# Hx711_schematic_V1_r1_0.net
KiCad netlist of a schematic drawn in EAGLE
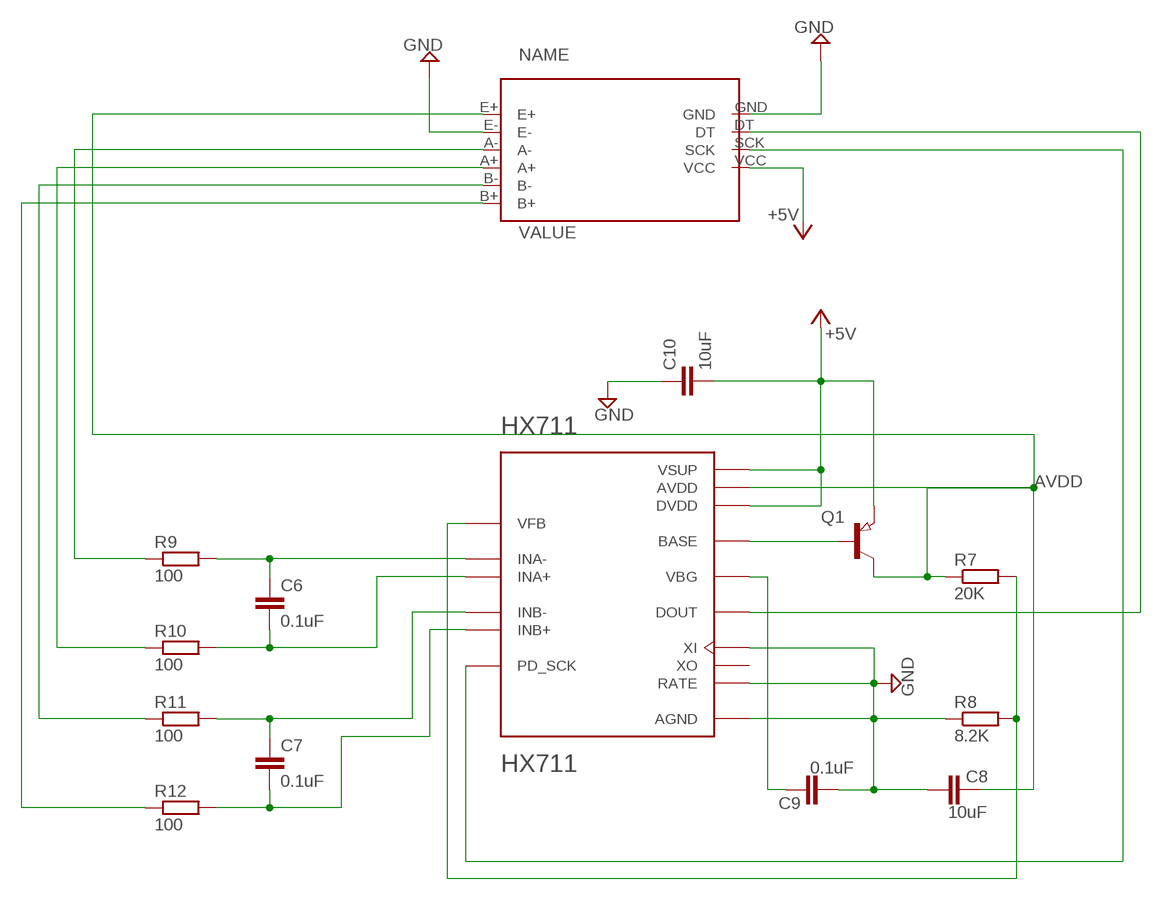
[diagram p0: schematic, sheet 1]

(export (version "E")
  (design (tool "Eeschema 10.0.6"))
  (components
    (comp (ref "C6")
      (value "0.1uF")
      (footprint "eagle-import:C2.5-2")
      (libsource (lib "eagle-import") (part "C2.5/2"))
    )
    (comp (ref "C7")
      (value "0.1uF")
      (footprint "eagle-import:C2.5-2")
      (libsource (lib "eagle-import") (part "C2.5/2"))
    )
    (comp (ref "C8")
      (value "10uF")
      (footprint "eagle-import:C2.5-2")
      (libsource (lib "eagle-import") (part "C2.5/2"))
    )
    (comp (ref "C9")
      (value "0.1uF")
      (footprint "eagle-import:C2.5-2")
      (libsource (lib "eagle-import") (part "C2.5/2"))
    )
    (comp (ref "C10")
      (value "10uF")
      (footprint "eagle-import:C2.5-2")
      (libsource (lib "eagle-import") (part "C2.5/2"))
    )
    (comp (ref "HX711")
      (value "HX711")
      (footprint "eagle-import:SOP127P600X180-16N")
      (fields (field (name "MF") "AVIA SEMICONDUCTOR"))
      (libsource (lib "eagle-import") (part "HX711"))
    )
    (comp (ref "Q1")
      (value "PNP-TRANSISTOR_SOT23")
      (footprint "eagle-import:SOT23")
      (libsource (lib "eagle-import") (part "PNP-TRANSISTOR_SOT23"))
    )
    (comp (ref "R7")
      (value "20K")
      (footprint "eagle-import:R0603")
      (libsource (lib "eagle-import") (part "R-EU_R0603"))
    )
    (comp (ref "R8")
      (value "8.2K")
      (footprint "eagle-import:R0603")
      (libsource (lib "eagle-import") (part "R-EU_R0603"))
    )
    (comp (ref "R9")
      (value "100")
      (footprint "eagle-import:R0603")
      (libsource (lib "eagle-import") (part "R-EU_R0603"))
    )
    (comp (ref "R10")
      (value "100")
      (footprint "eagle-import:R0603")
      (libsource (lib "eagle-import") (part "R-EU_R0603"))
    )
    (comp (ref "R11")
      (value "100")
      (footprint "eagle-import:R0603")
      (libsource (lib "eagle-import") (part "R-EU_R0603"))
    )
    (comp (ref "R12")
      (value "100")
      (footprint "eagle-import:R0603")
      (libsource (lib "eagle-import") (part "R-EU_R0603"))
    )
    (comp (ref "U$1")
      (value "HX711A")
      (footprint "eagle-import:HX711")
      (libsource (lib "eagle-import") (part "HX711A"))
    )
  )
  (nets
    (net (code "1") (name "+5V") (class "Default")
      (node (ref "C10") (pin "2") (pinfunction "2_2") (pintype "passive"))
      (node (ref "HX711") (pin "1") (pinfunction "VSUP_1") (pintype "power_in"))
      (node (ref "HX711") (pin "16") (pinfunction "DVDD_16") (pintype "power_in"))
      (node (ref "Q1") (pin "2") (pinfunction "E_2") (pintype "passive"))
      (node (ref "U$1") (pin "VCC") (pinfunction "VCC_VCC") (pintype "bidirectional"))
    )
    (net (code "2") (name "/AVDD") (class "Default")
      (node (ref "C8") (pin "1") (pinfunction "1_1") (pintype "passive"))
      (node (ref "HX711") (pin "3") (pinfunction "AVDD_3") (pintype "power_in"))
      (node (ref "Q1") (pin "3") (pinfunction "C_3") (pintype "passive"))
      (node (ref "R7") (pin "1") (pinfunction "1_1") (pintype "passive"))
      (node (ref "U$1") (pin "E+") (pinfunction "E+_E+") (pintype "bidirectional"))
    )
    (net (code "3") (name "GND") (class "Default")
      (node (ref "C10") (pin "1") (pinfunction "1_1") (pintype "passive"))
      (node (ref "C8") (pin "2") (pinfunction "2_2") (pintype "passive"))
      (node (ref "C9") (pin "2") (pinfunction "2_2") (pintype "passive"))
      (node (ref "HX711") (pin "14") (pinfunction "XI_14") (pintype "input"))
      (node (ref "HX711") (pin "15") (pinfunction "RATE_15") (pintype "input"))
      (node (ref "HX711") (pin "5") (pinfunction "AGND_5") (pintype "power_in"))
      (node (ref "R8") (pin "1") (pinfunction "1_1") (pintype "passive"))
      (node (ref "U$1") (pin "E-") (pinfunction "E-_E-") (pintype "bidirectional"))
      (node (ref "U$1") (pin "GND") (pinfunction "GND_GND") (pintype "bidirectional"))
    )
    (net (code "4") (name "Net-(HX711-BASE)") (class "Default")
      (node (ref "HX711") (pin "2") (pinfunction "BASE_2") (pintype "output"))
      (node (ref "Q1") (pin "1") (pinfunction "B_1") (pintype "passive"))
    )
    (net (code "5") (name "Net-(HX711-DOUT)") (class "Default")
      (node (ref "HX711") (pin "12") (pinfunction "DOUT_12") (pintype "output"))
      (node (ref "U$1") (pin "DT") (pinfunction "DT_DT") (pintype "bidirectional"))
    )
    (net (code "6") (name "Net-(HX711-INA+)") (class "Default")
      (node (ref "C6") (pin "2") (pinfunction "2_2") (pintype "passive"))
      (node (ref "HX711") (pin "8") (pinfunction "INA+_8") (pintype "input"))
      (node (ref "R10") (pin "2") (pinfunction "2_2") (pintype "passive"))
    )
    (net (code "7") (name "Net-(HX711-INA-)") (class "Default")
      (node (ref "C6") (pin "1") (pinfunction "1_1") (pintype "passive"))
      (node (ref "HX711") (pin "7") (pinfunction "INA-_7") (pintype "input"))
      (node (ref "R9") (pin "2") (pinfunction "2_2") (pintype "passive"))
    )
    (net (code "8") (name "Net-(HX711-INB+)") (class "Default")
      (node (ref "C7") (pin "2") (pinfunction "2_2") (pintype "passive"))
      (node (ref "HX711") (pin "10") (pinfunction "INB+_10") (pintype "input"))
      (node (ref "R12") (pin "2") (pinfunction "2_2") (pintype "passive"))
    )
    (net (code "9") (name "Net-(HX711-INB-)") (class "Default")
      (node (ref "C7") (pin "1") (pinfunction "1_1") (pintype "passive"))
      (node (ref "HX711") (pin "9") (pinfunction "INB-_9") (pintype "input"))
      (node (ref "R11") (pin "2") (pinfunction "2_2") (pintype "passive"))
    )
    (net (code "10") (name "Net-(HX711-PD_SCK)") (class "Default")
      (node (ref "HX711") (pin "11") (pinfunction "PD_SCK_11") (pintype "input"))
      (node (ref "U$1") (pin "SCK") (pinfunction "SCK_SCK") (pintype "bidirectional"))
    )
    (net (code "11") (name "Net-(HX711-VBG)") (class "Default")
      (node (ref "C9") (pin "1") (pinfunction "1_1") (pintype "passive"))
      (node (ref "HX711") (pin "6") (pinfunction "VBG_6") (pintype "output"))
    )
    (net (code "12") (name "Net-(HX711-VFB)") (class "Default")
      (node (ref "HX711") (pin "4") (pinfunction "VFB_4") (pintype "input"))
      (node (ref "R7") (pin "2") (pinfunction "2_2") (pintype "passive"))
      (node (ref "R8") (pin "2") (pinfunction "2_2") (pintype "passive"))
    )
    (net (code "13") (name "Net-(R9-Pad1)") (class "Default")
      (node (ref "R9") (pin "1") (pinfunction "1_1") (pintype "passive"))
      (node (ref "U$1") (pin "A-") (pinfunction "A-_A-") (pintype "bidirectional"))
    )
    (net (code "14") (name "Net-(R10-Pad1)") (class "Default")
      (node (ref "R10") (pin "1") (pinfunction "1_1") (pintype "passive"))
      (node (ref "U$1") (pin "A+") (pinfunction "A+_A+") (pintype "bidirectional"))
    )
    (net (code "15") (name "Net-(R11-Pad1)") (class "Default")
      (node (ref "R11") (pin "1") (pinfunction "1_1") (pintype "passive"))
      (node (ref "U$1") (pin "B-") (pinfunction "B-_B-") (pintype "bidirectional"))
    )
    (net (code "16") (name "Net-(R12-Pad1)") (class "Default")
      (node (ref "R12") (pin "1") (pinfunction "1_1") (pintype "passive"))
      (node (ref "U$1") (pin "B+") (pinfunction "B+_B+") (pintype "bidirectional"))
    )
    (net (code "17") (name "unconnected-(HX711-XO-Pad13)") (class "Default")
      (node (ref "HX711") (pin "13") (pinfunction "XO_13") (pintype "output"))
    )
  )
)
